# ps2.net
KiCad netlist of a schematic drawn in EAGLE
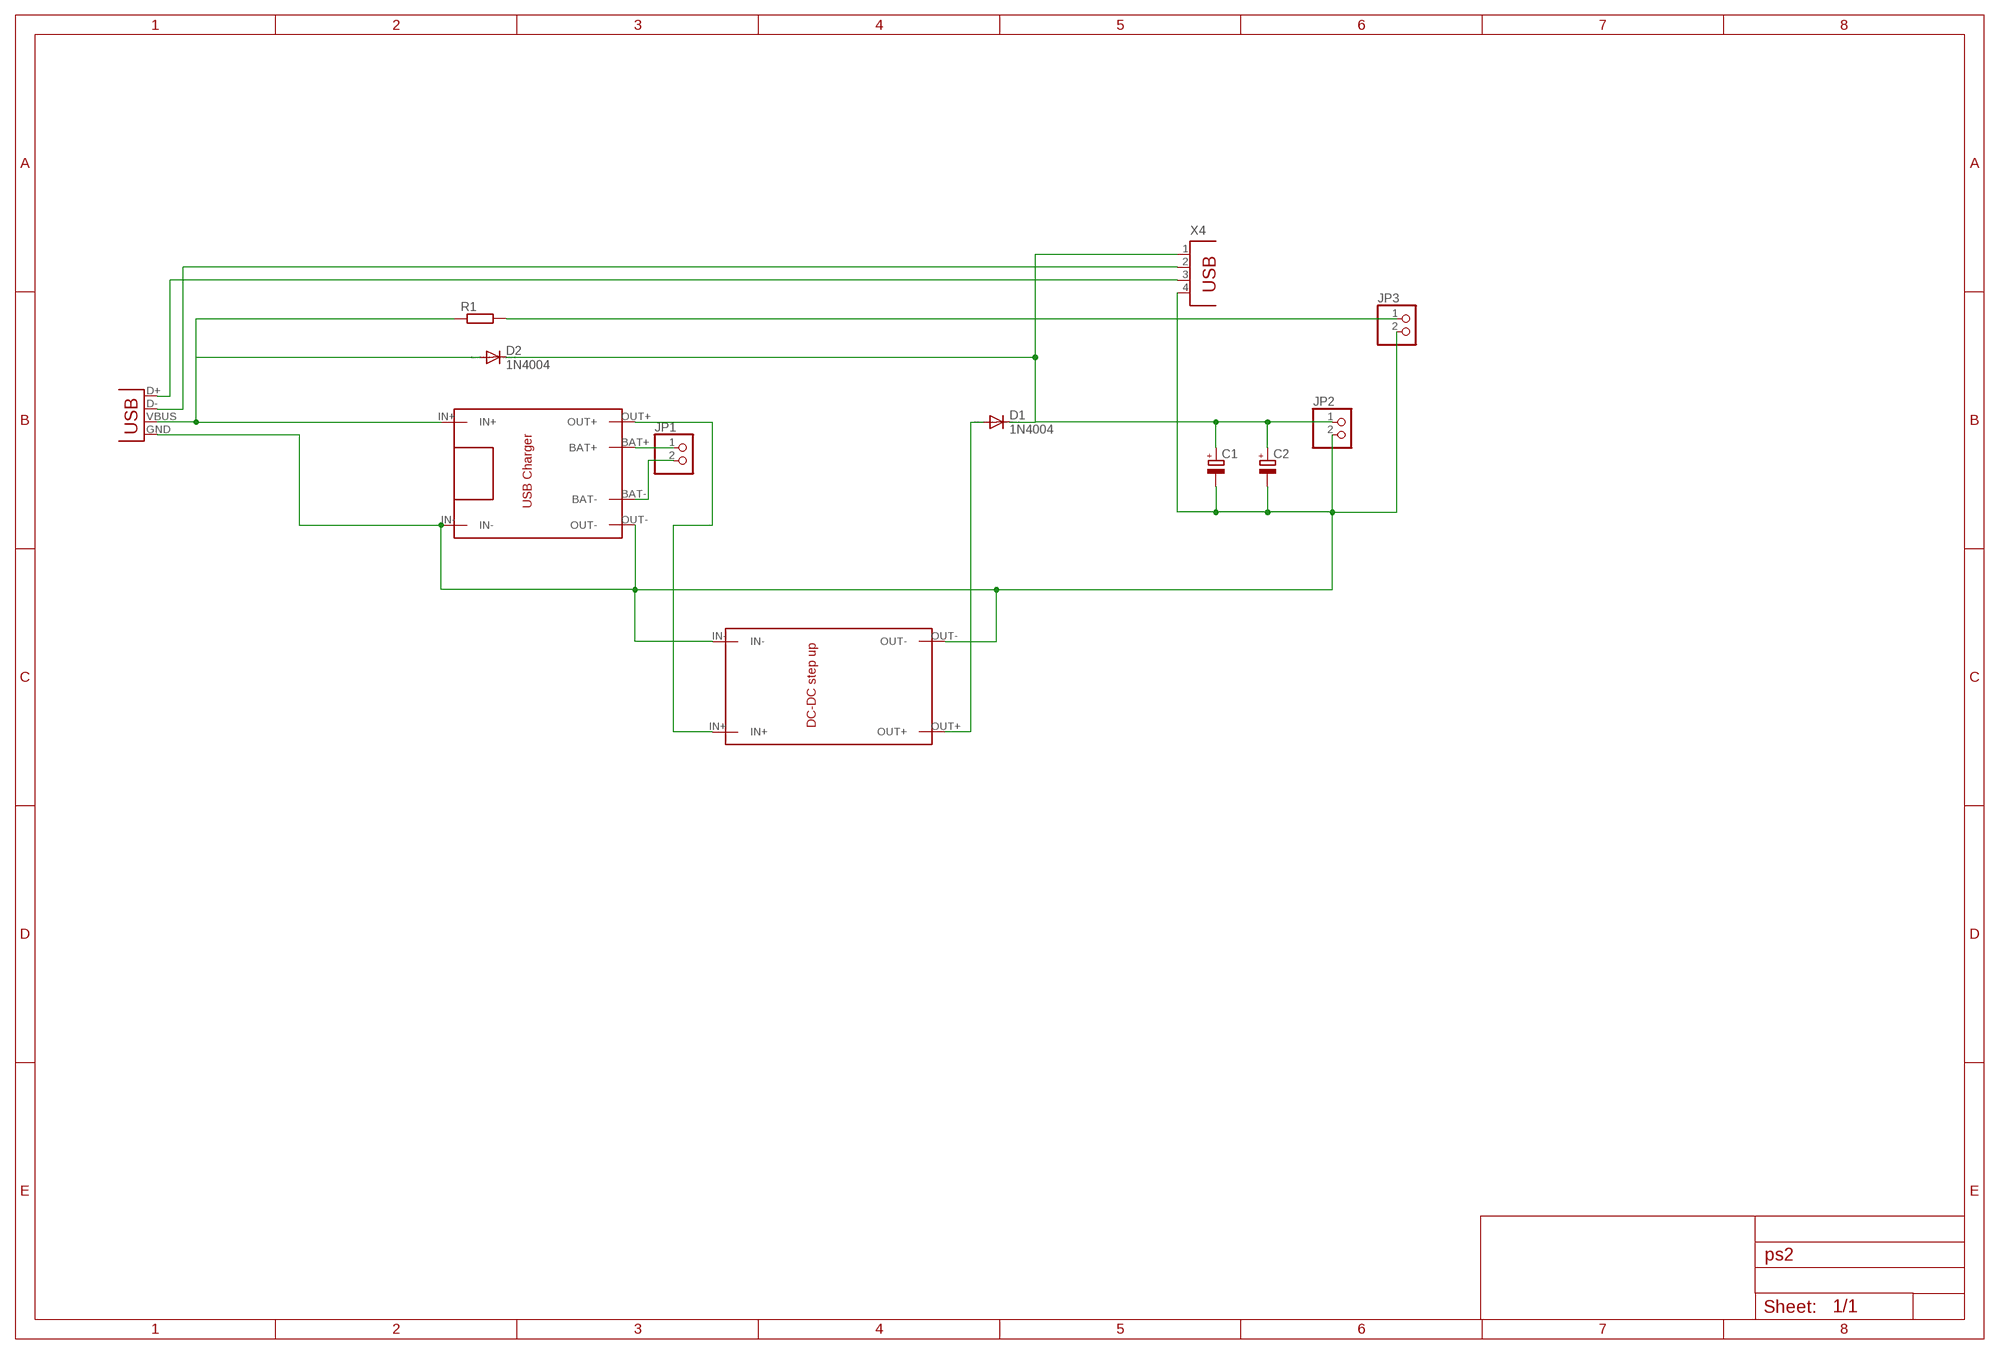
[diagram p0: schematic, sheet 1]

(export (version "E")
  (design (tool "Eeschema 10.0.6"))
  (components
    (comp (ref "C1")
      (value "CPOL-EUE5-10.5")
      (footprint "eagle-import:E5-10,5")
      (libsource (lib "eagle-import") (part "CPOL-EUE5-10.5"))
    )
    (comp (ref "C2")
      (value "CPOL-EUE5-10.5")
      (footprint "eagle-import:E5-10,5")
      (libsource (lib "eagle-import") (part "CPOL-EUE5-10.5"))
    )
    (comp (ref "D1")
      (value "1N4004")
      (footprint "eagle-import:DO41-10")
      (libsource (lib "eagle-import") (part "1N4004"))
    )
    (comp (ref "D2")
      (value "1N4004")
      (footprint "eagle-import:DO41-10")
      (libsource (lib "eagle-import") (part "1N4004"))
    )
    (comp (ref "JP1")
      (value "PINHD-1X2")
      (footprint "eagle-import:1X02")
      (libsource (lib "eagle-import") (part "PINHD-1X2"))
    )
    (comp (ref "JP2")
      (value "PINHD-1X2")
      (footprint "eagle-import:1X02")
      (libsource (lib "eagle-import") (part "PINHD-1X2"))
    )
    (comp (ref "JP3")
      (value "PINHD-1X2")
      (footprint "eagle-import:1X02")
      (libsource (lib "eagle-import") (part "PINHD-1X2"))
    )
    (comp (ref "R1")
      (value "R-EU_0207/10")
      (footprint "eagle-import:0207_10")
      (libsource (lib "eagle-import") (part "R-EU_0207/10"))
    )
    (comp (ref "U$1")
      (value "TP4056")
      (footprint "eagle-import:TP4056")
      (libsource (lib "eagle-import") (part "TP4056"))
    )
    (comp (ref "U$3")
      (value "DC-DC_STEPUP")
      (footprint "eagle-import:DC-DC_STEPUP")
      (libsource (lib "eagle-import") (part "DC-DC_STEPUP"))
    )
    (comp (ref "X3")
      (value "USBPTH")
      (footprint "eagle-import:USB-B-PTH")
      (libsource (lib "eagle-import") (part "USBPTH"))
    )
    (comp (ref "X4")
      (value "PN87520")
      (footprint "eagle-import:PN87520")
      (libsource (lib "eagle-import") (part "PN87520"))
    )
  )
  (nets
    (net (code "1") (name "Net-(C1-Pad+)") (class "Default")
      (node (ref "C1") (pin "+") (pinfunction "+_+") (pintype "passive"))
      (node (ref "C2") (pin "+") (pinfunction "+_+") (pintype "passive"))
      (node (ref "D1") (pin "C") (pinfunction "C_C") (pintype "passive"))
      (node (ref "D2") (pin "C") (pinfunction "C_C") (pintype "passive"))
      (node (ref "JP2") (pin "1") (pinfunction "1_1") (pintype "passive"))
      (node (ref "X4") (pin "1") (pinfunction "1_1") (pintype "passive"))
    )
    (net (code "2") (name "Net-(C1-Pad-)") (class "Default")
      (node (ref "C1") (pin "-") (pinfunction "-_-") (pintype "passive"))
      (node (ref "C2") (pin "-") (pinfunction "-_-") (pintype "passive"))
      (node (ref "JP2") (pin "2") (pinfunction "2_2") (pintype "passive"))
      (node (ref "JP3") (pin "2") (pinfunction "2_2") (pintype "passive"))
      (node (ref "U$1") (pin "IN-") (pinfunction "IN-_IN-") (pintype "bidirectional"))
      (node (ref "U$1") (pin "OUT-") (pinfunction "OUT-_OUT-") (pintype "bidirectional"))
      (node (ref "U$3") (pin "IN-") (pinfunction "IN-_IN-") (pintype "bidirectional"))
      (node (ref "U$3") (pin "OUT-") (pinfunction "OUT-_OUT-") (pintype "bidirectional"))
      (node (ref "X3") (pin "GND") (pinfunction "GND_GND") (pintype "bidirectional"))
      (node (ref "X4") (pin "4") (pinfunction "4_4") (pintype "passive"))
    )
    (net (code "3") (name "Net-(D1-PadA)") (class "Default")
      (node (ref "D1") (pin "A") (pinfunction "A_A") (pintype "passive"))
      (node (ref "U$3") (pin "OUT+") (pinfunction "OUT+_OUT+") (pintype "bidirectional"))
    )
    (net (code "4") (name "Net-(D2-PadA)") (class "Default")
      (node (ref "D2") (pin "A") (pinfunction "A_A") (pintype "passive"))
      (node (ref "R1") (pin "1") (pinfunction "1_1") (pintype "passive"))
      (node (ref "U$1") (pin "IN+") (pinfunction "IN+_IN+") (pintype "bidirectional"))
      (node (ref "X3") (pin "VBUS") (pinfunction "VBUS_VBUS") (pintype "bidirectional"))
    )
    (net (code "5") (name "Net-(JP1-Pad1)") (class "Default")
      (node (ref "JP1") (pin "1") (pinfunction "1_1") (pintype "passive"))
      (node (ref "U$1") (pin "BAT+") (pinfunction "BAT+_BAT+") (pintype "bidirectional"))
    )
    (net (code "6") (name "Net-(JP1-Pad2)") (class "Default")
      (node (ref "JP1") (pin "2") (pinfunction "2_2") (pintype "passive"))
      (node (ref "U$1") (pin "BAT-") (pinfunction "BAT-_BAT-") (pintype "bidirectional"))
    )
    (net (code "7") (name "Net-(JP3-Pad1)") (class "Default")
      (node (ref "JP3") (pin "1") (pinfunction "1_1") (pintype "passive"))
      (node (ref "R1") (pin "2") (pinfunction "2_2") (pintype "passive"))
    )
    (net (code "8") (name "Net-(U$1-PadOUT+)") (class "Default")
      (node (ref "U$1") (pin "OUT+") (pinfunction "OUT+_OUT+") (pintype "bidirectional"))
      (node (ref "U$3") (pin "IN+") (pinfunction "IN+_IN+") (pintype "bidirectional"))
    )
    (net (code "9") (name "Net-(X3-PadD+)") (class "Default")
      (node (ref "X3") (pin "D+") (pinfunction "D+_D+") (pintype "bidirectional"))
      (node (ref "X4") (pin "3") (pinfunction "3_3") (pintype "passive"))
    )
    (net (code "10") (name "Net-(X3-PadD-)") (class "Default")
      (node (ref "X3") (pin "D-") (pinfunction "D-_D-") (pintype "bidirectional"))
      (node (ref "X4") (pin "2") (pinfunction "2_2") (pintype "passive"))
    )
  )
)
